# winglet.net
KiCad netlist of a schematic drawn in EAGLE
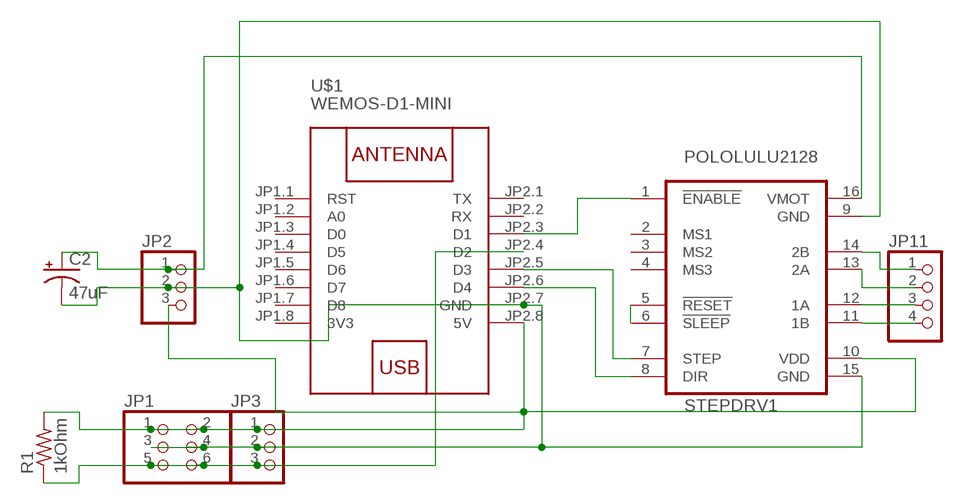
[diagram p0: schematic, sheet 1]

(export (version "E")
  (design (tool "Eeschema 10.0.6"))
  (components
    (comp (ref "C2")
      (value "47uF")
      (footprint "eagle-import:PANASONIC_D")
      (libsource (lib "eagle-import") (part "47UF-POLAR-PANASONIC_D-35V-20%"))
    )
    (comp (ref "JP1")
      (value "PINHD-2X3")
      (footprint "eagle-import:2X03")
      (libsource (lib "eagle-import") (part "PINHD-2X3"))
    )
    (comp (ref "JP2")
      (value "PINHD-1X3/90")
      (footprint "eagle-import:1X03_90")
      (libsource (lib "eagle-import") (part "PINHD-1X3/90"))
    )
    (comp (ref "JP3")
      (value "PINHD-1X3")
      (footprint "eagle-import:1X03")
      (libsource (lib "eagle-import") (part "PINHD-1X3"))
    )
    (comp (ref "JP11")
      (value "PINHD-1X4/90")
      (footprint "eagle-import:1X04_90")
      (libsource (lib "eagle-import") (part "PINHD-1X4/90"))
    )
    (comp (ref "R1")
      (value "1kOhm")
      (footprint "eagle-import:M1206")
      (libsource (lib "eagle-import") (part "R-US_M1206"))
    )
    (comp (ref "STEPDRV1")
      (value "POLOLULU2128")
      (footprint "eagle-import:POLOLULU2128")
      (libsource (lib "eagle-import") (part "POLOLULU2128"))
    )
    (comp (ref "U$1")
      (value "WEMOS-D1-MINI")
      (footprint "eagle-import:WEMOS-D1-MINI")
      (libsource (lib "eagle-import") (part "WEMOS-D1-MINI"))
    )
  )
  (nets
    (net (code "1") (name "/3V3") (class "Default")
      (node (ref "U$1") (pin "JP1.8") (pinfunction "3V3_JP1.8") (pintype "power_in"))
    )
    (net (code "2") (name "Net-(STEPDRV1-1A)") (class "Default")
      (node (ref "JP11") (pin "3") (pinfunction "3_3") (pintype "passive"))
      (node (ref "STEPDRV1") (pin "12") (pinfunction "1A_12") (pintype "output"))
    )
    (net (code "3") (name "Net-(STEPDRV1-1B)") (class "Default")
      (node (ref "JP11") (pin "4") (pinfunction "4_4") (pintype "passive"))
      (node (ref "STEPDRV1") (pin "11") (pinfunction "1B_11") (pintype "output"))
    )
    (net (code "4") (name "Net-(STEPDRV1-2A)") (class "Default")
      (node (ref "JP11") (pin "2") (pinfunction "2_2") (pintype "passive"))
      (node (ref "STEPDRV1") (pin "13") (pinfunction "2A_13") (pintype "output"))
    )
    (net (code "5") (name "Net-(STEPDRV1-2B)") (class "Default")
      (node (ref "JP11") (pin "1") (pinfunction "1_1") (pintype "passive"))
      (node (ref "STEPDRV1") (pin "14") (pinfunction "2B_14") (pintype "output"))
    )
    (net (code "6") (name "Net-(STEPDRV1-DIR)") (class "Default")
      (node (ref "STEPDRV1") (pin "8") (pinfunction "DIR_8") (pintype "input"))
      (node (ref "U$1") (pin "JP2.6") (pinfunction "D4_JP2.6") (pintype "bidirectional"))
    )
    (net (code "7") (name "Net-(STEPDRV1-STEP)") (class "Default")
      (node (ref "STEPDRV1") (pin "7") (pinfunction "STEP_7") (pintype "input"))
      (node (ref "U$1") (pin "JP2.5") (pinfunction "D3_JP2.5") (pintype "bidirectional"))
    )
    (net (code "8") (name "Net-(STEPDRV1-VDD)") (class "Default")
      (node (ref "JP1") (pin "1") (pinfunction "1_1") (pintype "passive"))
      (node (ref "JP1") (pin "2") (pinfunction "2_2") (pintype "passive"))
      (node (ref "JP2") (pin "3") (pinfunction "3_3") (pintype "passive"))
      (node (ref "JP3") (pin "1") (pinfunction "1_1") (pintype "passive"))
      (node (ref "R1") (pin "2") (pinfunction "2_2") (pintype "passive"))
      (node (ref "STEPDRV1") (pin "10") (pinfunction "VDD_10") (pintype "power_in"))
      (node (ref "U$1") (pin "JP2.8") (pinfunction "5V_JP2.8") (pintype "power_in"))
    )
    (net (code "9") (name "Net-(STEPDRV1-VMOT)") (class "Default")
      (node (ref "C2") (pin "+") (pinfunction "+_+") (pintype "passive"))
      (node (ref "JP2") (pin "1") (pinfunction "1_1") (pintype "passive"))
      (node (ref "STEPDRV1") (pin "16") (pinfunction "VMOT_16") (pintype "power_in"))
    )
    (net (code "10") (name "Net-(STEPDRV1-~{ENABLE})") (class "Default")
      (node (ref "STEPDRV1") (pin "1") (pinfunction "~{ENABLE}_1") (pintype "input"))
      (node (ref "U$1") (pin "JP2.3") (pinfunction "D1_JP2.3") (pintype "bidirectional"))
    )
    (net (code "11") (name "Net-(STEPDRV1-~{RESET})") (class "Default")
      (node (ref "STEPDRV1") (pin "5") (pinfunction "~{RESET}_5") (pintype "input"))
      (node (ref "STEPDRV1") (pin "6") (pinfunction "~{SLEEP}_6") (pintype "input"))
    )
    (net (code "12") (name "Net-(U$1-D2)") (class "Default")
      (node (ref "JP1") (pin "5") (pinfunction "5_5") (pintype "passive"))
      (node (ref "JP1") (pin "6") (pinfunction "6_6") (pintype "passive"))
      (node (ref "JP3") (pin "3") (pinfunction "3_3") (pintype "passive"))
      (node (ref "R1") (pin "1") (pinfunction "1_1") (pintype "passive"))
      (node (ref "U$1") (pin "JP2.4") (pinfunction "D2_JP2.4") (pintype "bidirectional"))
    )
    (net (code "13") (name "Net-(U$1-GND)") (class "Default")
      (node (ref "C2") (pin "-") (pinfunction "-_-") (pintype "passive"))
      (node (ref "JP1") (pin "3") (pinfunction "3_3") (pintype "passive"))
      (node (ref "JP1") (pin "4") (pinfunction "4_4") (pintype "passive"))
      (node (ref "JP2") (pin "2") (pinfunction "2_2") (pintype "passive"))
      (node (ref "JP3") (pin "2") (pinfunction "2_2") (pintype "passive"))
      (node (ref "STEPDRV1") (pin "15") (pinfunction "GND_15") (pintype "power_in"))
      (node (ref "STEPDRV1") (pin "9") (pinfunction "GND_9") (pintype "power_in"))
      (node (ref "U$1") (pin "JP2.7") (pinfunction "GND_JP2.7") (pintype "power_in"))
    )
    (net (code "14") (name "unconnected-(STEPDRV1-MS1-Pad2)") (class "Default")
      (node (ref "STEPDRV1") (pin "2") (pinfunction "MS1_2") (pintype "input"))
    )
    (net (code "15") (name "unconnected-(STEPDRV1-MS2-Pad3)") (class "Default")
      (node (ref "STEPDRV1") (pin "3") (pinfunction "MS2_3") (pintype "input"))
    )
    (net (code "16") (name "unconnected-(STEPDRV1-MS3-Pad4)") (class "Default")
      (node (ref "STEPDRV1") (pin "4") (pinfunction "MS3_4") (pintype "input"))
    )
    (net (code "17") (name "unconnected-(U$1-A0-PadJP1.2)") (class "Default")
      (node (ref "U$1") (pin "JP1.2") (pinfunction "A0_JP1.2") (pintype "bidirectional"))
    )
    (net (code "18") (name "unconnected-(U$1-D0-PadJP1.3)") (class "Default")
      (node (ref "U$1") (pin "JP1.3") (pinfunction "D0_JP1.3") (pintype "bidirectional"))
    )
    (net (code "19") (name "unconnected-(U$1-D5-PadJP1.4)") (class "Default")
      (node (ref "U$1") (pin "JP1.4") (pinfunction "D5_JP1.4") (pintype "bidirectional"))
    )
    (net (code "20") (name "unconnected-(U$1-D6-PadJP1.5)") (class "Default")
      (node (ref "U$1") (pin "JP1.5") (pinfunction "D6_JP1.5") (pintype "bidirectional"))
    )
    (net (code "21") (name "unconnected-(U$1-D7-PadJP1.6)") (class "Default")
      (node (ref "U$1") (pin "JP1.6") (pinfunction "D7_JP1.6") (pintype "bidirectional"))
    )
    (net (code "22") (name "unconnected-(U$1-D8-PadJP1.7)") (class "Default")
      (node (ref "U$1") (pin "JP1.7") (pinfunction "D8_JP1.7") (pintype "bidirectional"))
    )
    (net (code "23") (name "unconnected-(U$1-RST-PadJP1.1)") (class "Default")
      (node (ref "U$1") (pin "JP1.1") (pinfunction "RST_JP1.1") (pintype "bidirectional"))
    )
    (net (code "24") (name "unconnected-(U$1-RX-PadJP2.2)") (class "Default")
      (node (ref "U$1") (pin "JP2.2") (pinfunction "RX_JP2.2") (pintype "bidirectional"))
    )
    (net (code "25") (name "unconnected-(U$1-TX-PadJP2.1)") (class "Default")
      (node (ref "U$1") (pin "JP2.1") (pinfunction "TX_JP2.1") (pintype "bidirectional"))
    )
  )
)
